# Adafruit_DVI_Sock_for_Pico.net
KiCad netlist of a schematic drawn in EAGLE
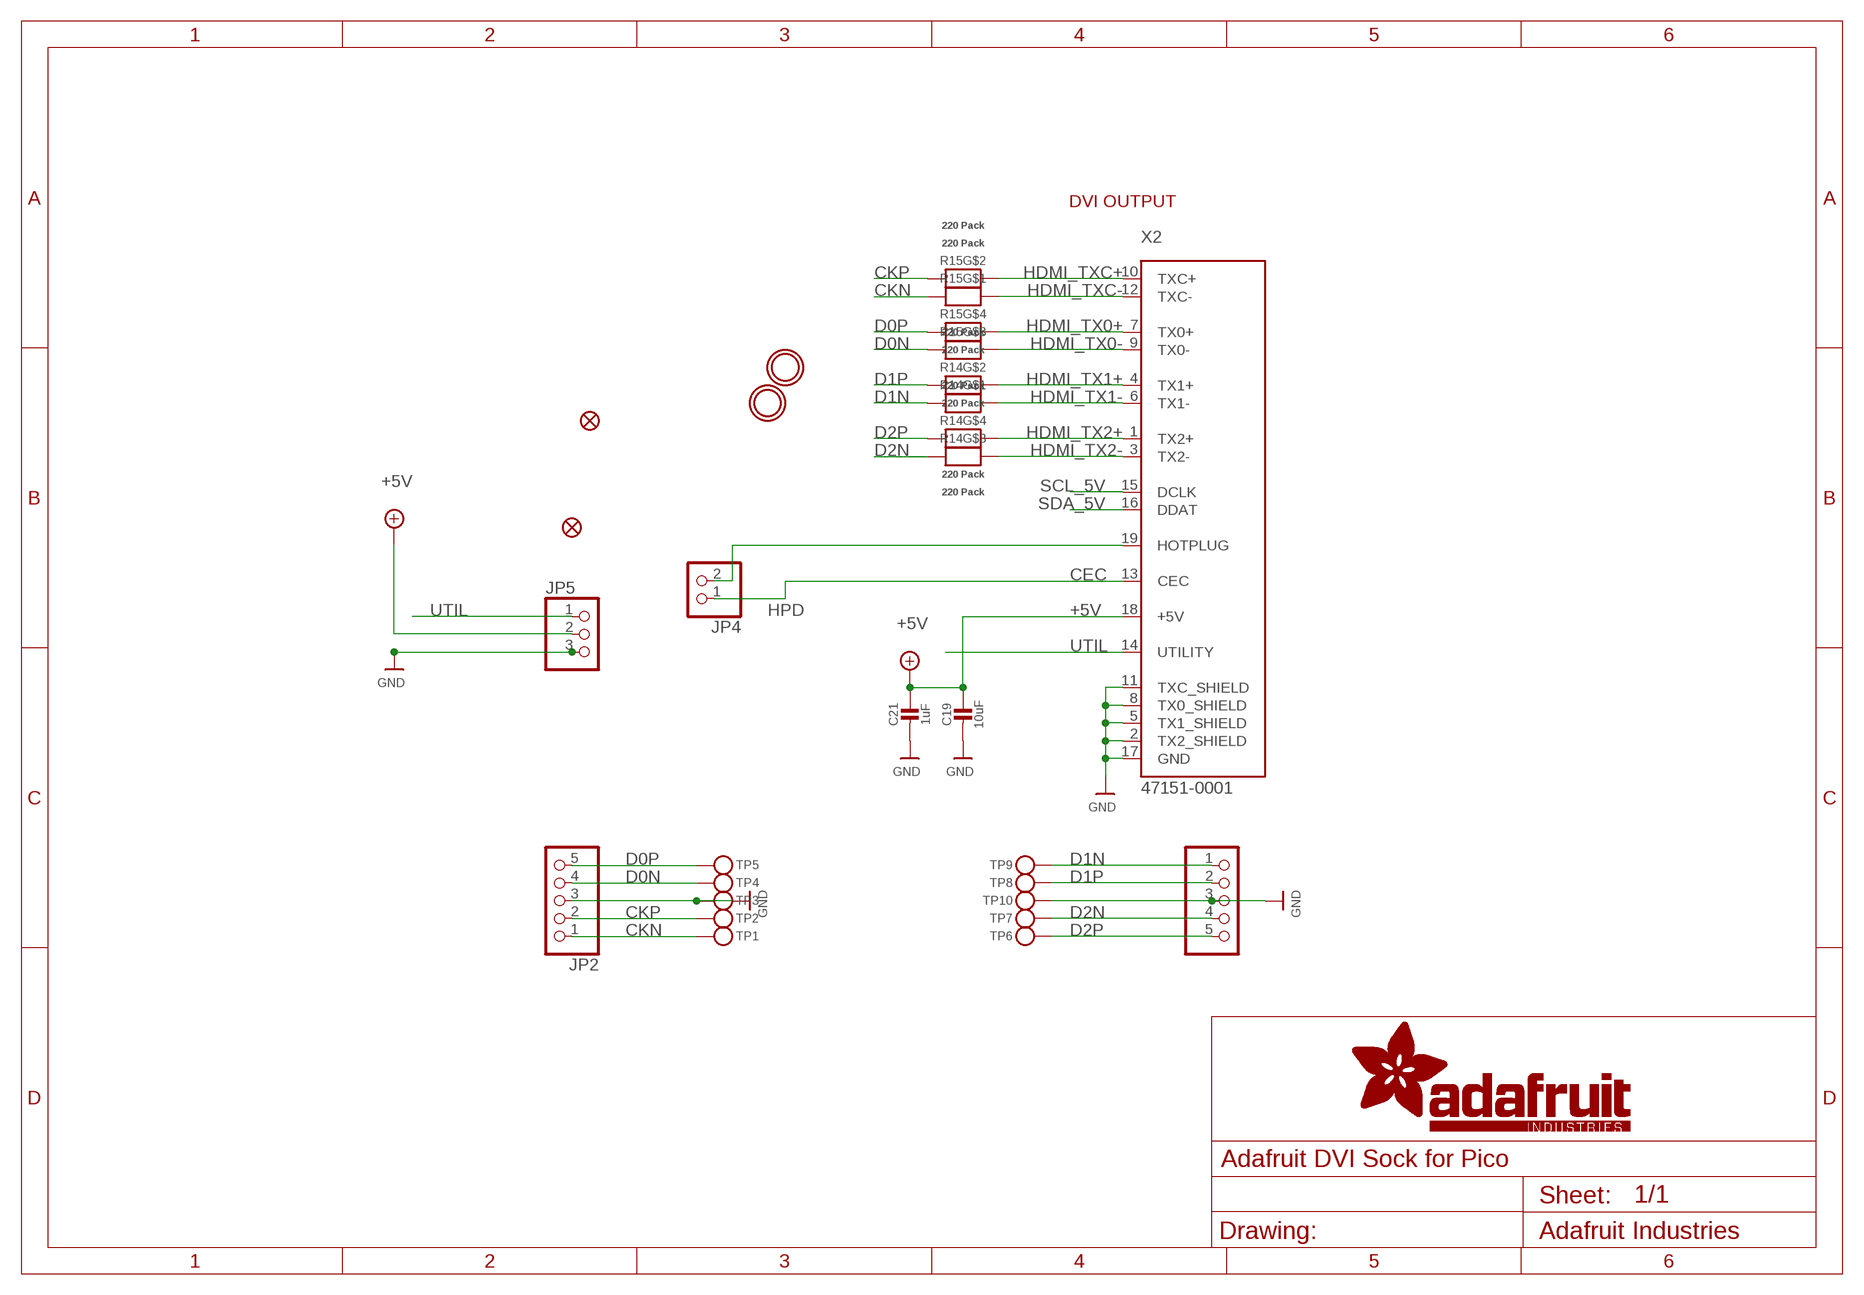
[diagram p0: schematic, sheet 1]

(export (version "E")
  (design (tool "Eeschema 10.0.6"))
  (components
    (comp (ref "C19")
      (value "10uF")
      (footprint "eagle-import:0805-NO")
      (fields (field (name "REV") "A"))
      (libsource (lib "eagle-import") (part "CAP_CERAMIC0805-NOOUTLINE"))
    )
    (comp (ref "C21")
      (value "1uF")
      (footprint "eagle-import:0603-NO")
      (libsource (lib "eagle-import") (part "CAP_CERAMIC0603_NO"))
    )
    (comp (ref "FID1")
      (value "FIDUCIAL_1MM")
      (footprint "eagle-import:FIDUCIAL_1MM")
      (libsource (lib "eagle-import") (part "FIDUCIAL_1MM"))
    )
    (comp (ref "FID2")
      (value "FIDUCIAL_1MM")
      (footprint "eagle-import:FIDUCIAL_1MM")
      (libsource (lib "eagle-import") (part "FIDUCIAL_1MM"))
    )
    (comp (ref "JP2")
      (value "HEADER-1X5")
      (footprint "eagle-import:1X05_OVAL")
      (libsource (lib "eagle-import") (part "HEADER-1X5"))
    )
    (comp (ref "JP3")
      (value "HEADER-1X5")
      (footprint "eagle-import:1X05_OVAL")
      (libsource (lib "eagle-import") (part "HEADER-1X5"))
    )
    (comp (ref "JP4")
      (value "HEADER-1X2ROUND")
      (footprint "eagle-import:1X02_ROUND")
      (libsource (lib "eagle-import") (part "HEADER-1X2ROUND"))
    )
    (comp (ref "JP5")
      (value "HEADER-1X3ROUND")
      (footprint "eagle-import:1X03_ROUND")
      (libsource (lib "eagle-import") (part "HEADER-1X3ROUND"))
    )
    (comp (ref "R14")
      (value "220 Pack")
      (footprint "eagle-import:RESPACK_4X0603")
      (libsource (lib "eagle-import") (part "RESISTOR_4PACK"))
    )
    (comp (ref "R15")
      (value "220 Pack")
      (footprint "eagle-import:RESPACK_4X0603")
      (libsource (lib "eagle-import") (part "RESISTOR_4PACK"))
    )
    (comp (ref "TP1")
      (value "TESTPOINT_1X3")
      (footprint "eagle-import:TESTPOINT_RECT_1X3MM")
      (libsource (lib "eagle-import") (part "TESTPOINT_1X3"))
    )
    (comp (ref "TP2")
      (value "TESTPOINT_1X3")
      (footprint "eagle-import:TESTPOINT_RECT_1X3MM")
      (libsource (lib "eagle-import") (part "TESTPOINT_1X3"))
    )
    (comp (ref "TP3")
      (value "TESTPOINT_1X3")
      (footprint "eagle-import:TESTPOINT_RECT_1X3MM")
      (libsource (lib "eagle-import") (part "TESTPOINT_1X3"))
    )
    (comp (ref "TP4")
      (value "TESTPOINT_1X3")
      (footprint "eagle-import:TESTPOINT_RECT_1X3MM")
      (libsource (lib "eagle-import") (part "TESTPOINT_1X3"))
    )
    (comp (ref "TP5")
      (value "TESTPOINT_1X3")
      (footprint "eagle-import:TESTPOINT_RECT_1X3MM")
      (libsource (lib "eagle-import") (part "TESTPOINT_1X3"))
    )
    (comp (ref "TP6")
      (value "TESTPOINT_1X3")
      (footprint "eagle-import:TESTPOINT_RECT_1X3MM")
      (libsource (lib "eagle-import") (part "TESTPOINT_1X3"))
    )
    (comp (ref "TP7")
      (value "TESTPOINT_1X3")
      (footprint "eagle-import:TESTPOINT_RECT_1X3MM")
      (libsource (lib "eagle-import") (part "TESTPOINT_1X3"))
    )
    (comp (ref "TP8")
      (value "TESTPOINT_1X3")
      (footprint "eagle-import:TESTPOINT_RECT_1X3MM")
      (libsource (lib "eagle-import") (part "TESTPOINT_1X3"))
    )
    (comp (ref "TP9")
      (value "TESTPOINT_1X3")
      (footprint "eagle-import:TESTPOINT_RECT_1X3MM")
      (libsource (lib "eagle-import") (part "TESTPOINT_1X3"))
    )
    (comp (ref "TP10")
      (value "TESTPOINT_1X3")
      (footprint "eagle-import:TESTPOINT_RECT_1X3MM")
      (libsource (lib "eagle-import") (part "TESTPOINT_1X3"))
    )
    (comp (ref "U$5")
      (value "MOUNTINGHOLE2.5")
      (footprint "eagle-import:MOUNTINGHOLE_2.5_PLATED")
      (libsource (lib "eagle-import") (part "MOUNTINGHOLE2.5"))
    )
    (comp (ref "U$6")
      (value "MOUNTINGHOLE2.5")
      (footprint "eagle-import:MOUNTINGHOLE_2.5_PLATED")
      (libsource (lib "eagle-import") (part "MOUNTINGHOLE2.5"))
    )
    (comp (ref "X2")
      (value "47151-0001")
      (footprint "eagle-import:HDMI_MOLEX_47151-0001")
      (libsource (lib "eagle-import") (part "HDMI_MOLEX_47151"))
    )
  )
  (nets
    (net (code "1") (name "+5V") (class "Default")
      (node (ref "C19") (pin "1") (pinfunction "1_1") (pintype "passive"))
      (node (ref "C21") (pin "1") (pinfunction "1_1") (pintype "passive"))
      (node (ref "JP5") (pin "2") (pinfunction "2_2") (pintype "passive"))
      (node (ref "X2") (pin "18") (pinfunction "+5V_18") (pintype "power_in"))
    )
    (net (code "2") (name "/CEC") (class "Default")
      (node (ref "JP4") (pin "1") (pinfunction "1_1") (pintype "passive"))
      (node (ref "X2") (pin "13") (pinfunction "CEC_13") (pintype "bidirectional"))
    )
    (net (code "3") (name "/CKN") (class "Default")
      (node (ref "JP2") (pin "1") (pinfunction "1_1") (pintype "passive"))
      (node (ref "R15") (pin "8") (pinfunction "2_8") (pintype "passive"))
      (node (ref "TP1") (pin "P$1") (pinfunction "P$1_P$1") (pintype "bidirectional"))
    )
    (net (code "4") (name "/CKP") (class "Default")
      (node (ref "JP2") (pin "2") (pinfunction "2_2") (pintype "passive"))
      (node (ref "R15") (pin "7") (pinfunction "2_7") (pintype "passive"))
      (node (ref "TP2") (pin "P$1") (pinfunction "P$1_P$1") (pintype "bidirectional"))
    )
    (net (code "5") (name "/D0N") (class "Default")
      (node (ref "JP2") (pin "4") (pinfunction "4_4") (pintype "passive"))
      (node (ref "R15") (pin "6") (pinfunction "2_6") (pintype "passive"))
      (node (ref "TP4") (pin "P$1") (pinfunction "P$1_P$1") (pintype "bidirectional"))
    )
    (net (code "6") (name "/D0P") (class "Default")
      (node (ref "JP2") (pin "5") (pinfunction "5_5") (pintype "passive"))
      (node (ref "R15") (pin "5") (pinfunction "2_5") (pintype "passive"))
      (node (ref "TP5") (pin "P$1") (pinfunction "P$1_P$1") (pintype "bidirectional"))
    )
    (net (code "7") (name "/D1N") (class "Default")
      (node (ref "JP3") (pin "1") (pinfunction "1_1") (pintype "passive"))
      (node (ref "R14") (pin "8") (pinfunction "2_8") (pintype "passive"))
      (node (ref "TP9") (pin "P$1") (pinfunction "P$1_P$1") (pintype "bidirectional"))
    )
    (net (code "8") (name "/D1P") (class "Default")
      (node (ref "JP3") (pin "2") (pinfunction "2_2") (pintype "passive"))
      (node (ref "R14") (pin "7") (pinfunction "2_7") (pintype "passive"))
      (node (ref "TP8") (pin "P$1") (pinfunction "P$1_P$1") (pintype "bidirectional"))
    )
    (net (code "9") (name "/D2N") (class "Default")
      (node (ref "JP3") (pin "4") (pinfunction "4_4") (pintype "passive"))
      (node (ref "R14") (pin "6") (pinfunction "2_6") (pintype "passive"))
      (node (ref "TP7") (pin "P$1") (pinfunction "P$1_P$1") (pintype "bidirectional"))
    )
    (net (code "10") (name "/D2P") (class "Default")
      (node (ref "JP3") (pin "5") (pinfunction "5_5") (pintype "passive"))
      (node (ref "R14") (pin "5") (pinfunction "2_5") (pintype "passive"))
      (node (ref "TP6") (pin "P$1") (pinfunction "P$1_P$1") (pintype "bidirectional"))
    )
    (net (code "11") (name "/HDMI_TX0+") (class "Default")
      (node (ref "R15") (pin "4") (pinfunction "1_4") (pintype "passive"))
      (node (ref "X2") (pin "7") (pinfunction "TX0+_7") (pintype "bidirectional"))
    )
    (net (code "12") (name "/HDMI_TX0-") (class "Default")
      (node (ref "R15") (pin "3") (pinfunction "1_3") (pintype "passive"))
      (node (ref "X2") (pin "9") (pinfunction "TX0-_9") (pintype "bidirectional"))
    )
    (net (code "13") (name "/HDMI_TX1+") (class "Default")
      (node (ref "R14") (pin "2") (pinfunction "1_2") (pintype "passive"))
      (node (ref "X2") (pin "4") (pinfunction "TX1+_4") (pintype "bidirectional"))
    )
    (net (code "14") (name "/HDMI_TX1-") (class "Default")
      (node (ref "R14") (pin "1") (pinfunction "1_1") (pintype "passive"))
      (node (ref "X2") (pin "6") (pinfunction "TX1-_6") (pintype "bidirectional"))
    )
    (net (code "15") (name "/HDMI_TX2+") (class "Default")
      (node (ref "R14") (pin "4") (pinfunction "1_4") (pintype "passive"))
      (node (ref "X2") (pin "1") (pinfunction "TX2+_1") (pintype "bidirectional"))
    )
    (net (code "16") (name "/HDMI_TX2-") (class "Default")
      (node (ref "R14") (pin "3") (pinfunction "1_3") (pintype "passive"))
      (node (ref "X2") (pin "3") (pinfunction "TX2-_3") (pintype "bidirectional"))
    )
    (net (code "17") (name "/HDMI_TXC+") (class "Default")
      (node (ref "R15") (pin "2") (pinfunction "1_2") (pintype "passive"))
      (node (ref "X2") (pin "10") (pinfunction "TXC+_10") (pintype "bidirectional"))
    )
    (net (code "18") (name "/HDMI_TXC-") (class "Default")
      (node (ref "R15") (pin "1") (pinfunction "1_1") (pintype "passive"))
      (node (ref "X2") (pin "12") (pinfunction "TXC-_12") (pintype "bidirectional"))
    )
    (net (code "19") (name "/HPD") (class "Default")
      (node (ref "JP4") (pin "2") (pinfunction "2_2") (pintype "passive"))
      (node (ref "X2") (pin "19") (pinfunction "HOTPLUG_19") (pintype "bidirectional"))
    )
    (net (code "20") (name "/SCL_5V") (class "Default")
      (node (ref "X2") (pin "15") (pinfunction "DCLK_15") (pintype "bidirectional"))
    )
    (net (code "21") (name "/SDA_5V") (class "Default")
      (node (ref "X2") (pin "16") (pinfunction "DDAT_16") (pintype "bidirectional"))
    )
    (net (code "22") (name "/UTIL") (class "Default")
      (node (ref "JP5") (pin "1") (pinfunction "1_1") (pintype "passive"))
      (node (ref "X2") (pin "14") (pinfunction "UTILITY_14") (pintype "bidirectional"))
    )
    (net (code "23") (name "GND") (class "Default")
      (node (ref "C19") (pin "2") (pinfunction "2_2") (pintype "passive"))
      (node (ref "C21") (pin "2") (pinfunction "2_2") (pintype "passive"))
      (node (ref "JP2") (pin "3") (pinfunction "3_3") (pintype "passive"))
      (node (ref "JP3") (pin "3") (pinfunction "3_3") (pintype "passive"))
      (node (ref "JP5") (pin "3") (pinfunction "3_3") (pintype "passive"))
      (node (ref "TP10") (pin "P$1") (pinfunction "P$1_P$1") (pintype "bidirectional"))
      (node (ref "TP3") (pin "P$1") (pinfunction "P$1_P$1") (pintype "bidirectional"))
      (node (ref "X2") (pin "11") (pinfunction "TXC_SHIELD_11") (pintype "power_in"))
      (node (ref "X2") (pin "17") (pinfunction "GND_17") (pintype "power_in"))
      (node (ref "X2") (pin "2") (pinfunction "TX2_SHIELD_2") (pintype "power_in"))
      (node (ref "X2") (pin "5") (pinfunction "TX1_SHIELD_5") (pintype "power_in"))
      (node (ref "X2") (pin "8") (pinfunction "TX0_SHIELD_8") (pintype "power_in"))
    )
  )
)
